# 3.net
KiCad netlist of a schematic drawn in Altium Designer
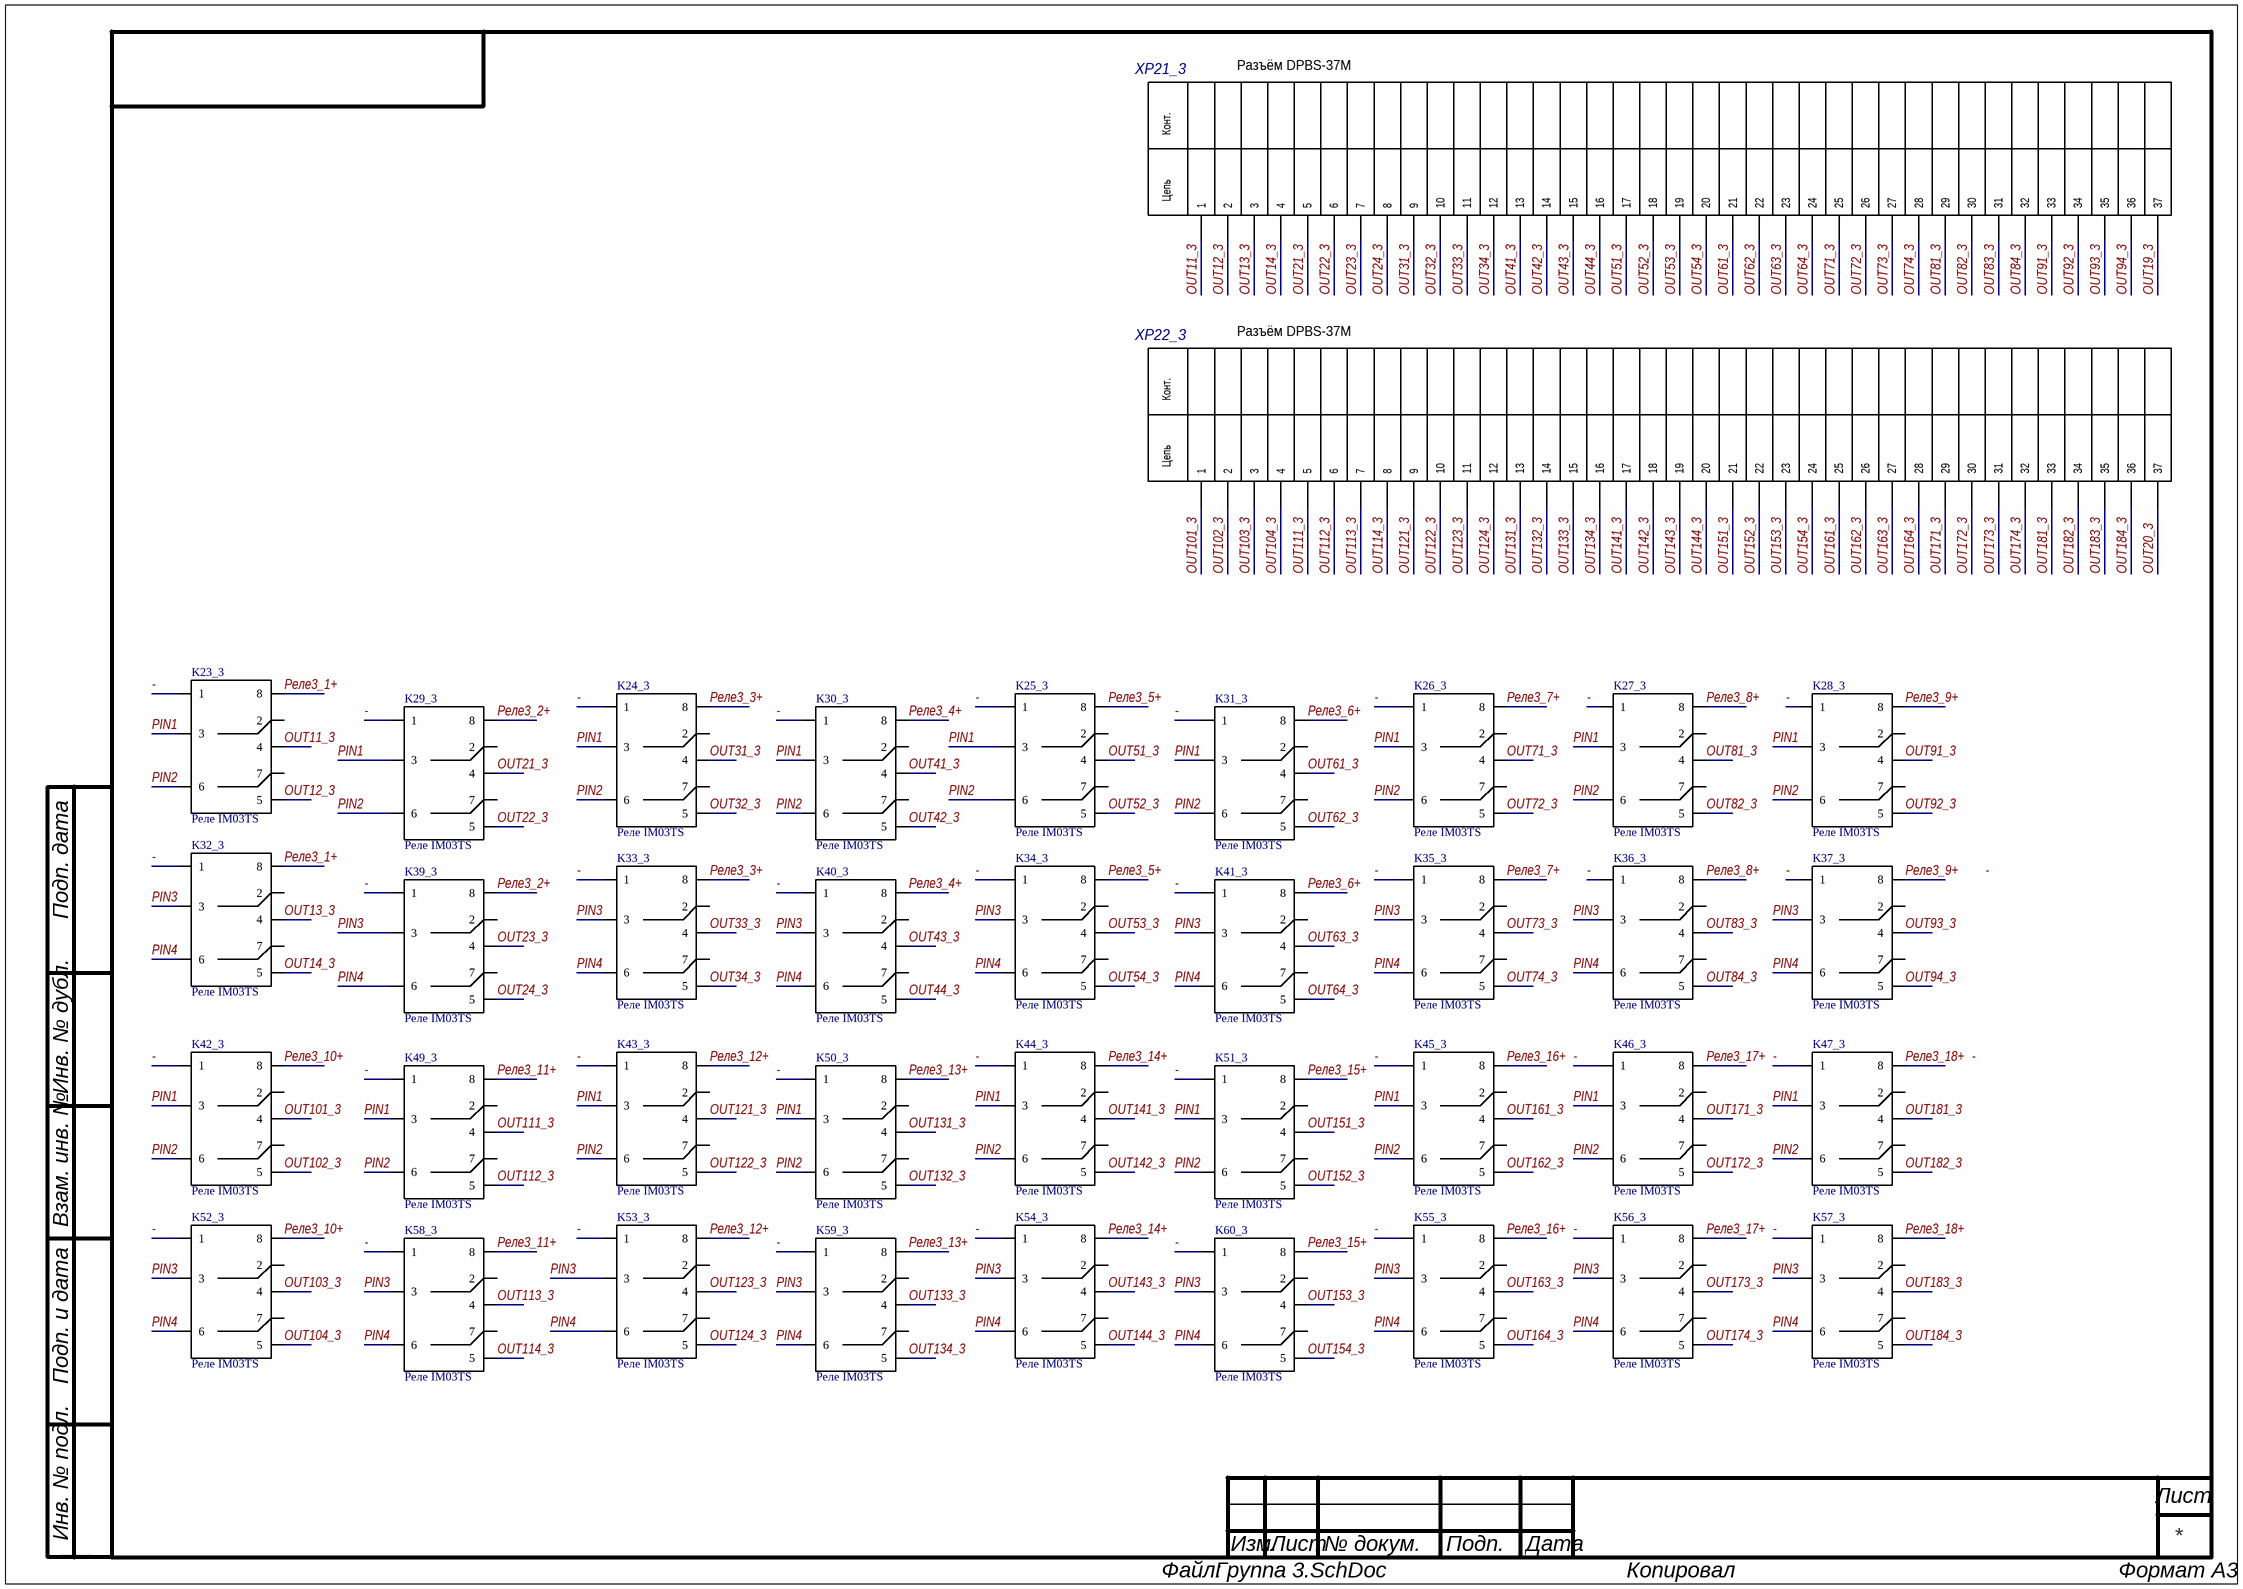
[diagram p0: Группа 3.SchDoc]

(export (version "E")
  (design (tool "Eeschema 10.0.6"))
  (components
    (comp (ref "K23_3")
      (value "Реле IM03TS")
      (footprint "IM03TS")
      (description "Реле")
      (libsource (lib "MainLibrary") (part "IM03TS"))
    )
    (comp (ref "K24_3")
      (value "Реле IM03TS")
      (footprint "IM03TS")
      (description "Реле")
      (libsource (lib "MainLibrary") (part "IM03TS"))
    )
    (comp (ref "K25_3")
      (value "Реле IM03TS")
      (footprint "IM03TS")
      (description "Реле")
      (libsource (lib "MainLibrary") (part "IM03TS"))
    )
    (comp (ref "K26_3")
      (value "Реле IM03TS")
      (footprint "IM03TS")
      (description "Реле")
      (libsource (lib "MainLibrary") (part "IM03TS"))
    )
    (comp (ref "K27_3")
      (value "Реле IM03TS")
      (footprint "IM03TS")
      (description "Реле")
      (libsource (lib "MainLibrary") (part "IM03TS"))
    )
    (comp (ref "K28_3")
      (value "Реле IM03TS")
      (footprint "IM03TS")
      (description "Реле")
      (libsource (lib "MainLibrary") (part "IM03TS"))
    )
    (comp (ref "K29_3")
      (value "Реле IM03TS")
      (footprint "IM03TS")
      (description "Реле")
      (libsource (lib "MainLibrary") (part "IM03TS"))
    )
    (comp (ref "K30_3")
      (value "Реле IM03TS")
      (footprint "IM03TS")
      (description "Реле")
      (libsource (lib "MainLibrary") (part "IM03TS"))
    )
    (comp (ref "K31_3")
      (value "Реле IM03TS")
      (footprint "IM03TS")
      (description "Реле")
      (libsource (lib "MainLibrary") (part "IM03TS"))
    )
    (comp (ref "K32_3")
      (value "Реле IM03TS")
      (footprint "IM03TS")
      (description "Реле")
      (libsource (lib "MainLibrary") (part "IM03TS"))
    )
    (comp (ref "K33_3")
      (value "Реле IM03TS")
      (footprint "IM03TS")
      (description "Реле")
      (libsource (lib "MainLibrary") (part "IM03TS"))
    )
    (comp (ref "K34_3")
      (value "Реле IM03TS")
      (footprint "IM03TS")
      (description "Реле")
      (libsource (lib "MainLibrary") (part "IM03TS"))
    )
    (comp (ref "K35_3")
      (value "Реле IM03TS")
      (footprint "IM03TS")
      (description "Реле")
      (libsource (lib "MainLibrary") (part "IM03TS"))
    )
    (comp (ref "K36_3")
      (value "Реле IM03TS")
      (footprint "IM03TS")
      (description "Реле")
      (libsource (lib "MainLibrary") (part "IM03TS"))
    )
    (comp (ref "K37_3")
      (value "Реле IM03TS")
      (footprint "IM03TS")
      (description "Реле")
      (libsource (lib "MainLibrary") (part "IM03TS"))
    )
    (comp (ref "K39_3")
      (value "Реле IM03TS")
      (footprint "IM03TS")
      (description "Реле")
      (libsource (lib "MainLibrary") (part "IM03TS"))
    )
    (comp (ref "K40_3")
      (value "Реле IM03TS")
      (footprint "IM03TS")
      (description "Реле")
      (libsource (lib "MainLibrary") (part "IM03TS"))
    )
    (comp (ref "K41_3")
      (value "Реле IM03TS")
      (footprint "IM03TS")
      (description "Реле")
      (libsource (lib "MainLibrary") (part "IM03TS"))
    )
    (comp (ref "K42_3")
      (value "Реле IM03TS")
      (footprint "IM03TS")
      (description "Реле")
      (libsource (lib "MainLibrary") (part "IM03TS"))
    )
    (comp (ref "K43_3")
      (value "Реле IM03TS")
      (footprint "IM03TS")
      (description "Реле")
      (libsource (lib "MainLibrary") (part "IM03TS"))
    )
    (comp (ref "K44_3")
      (value "Реле IM03TS")
      (footprint "IM03TS")
      (description "Реле")
      (libsource (lib "MainLibrary") (part "IM03TS"))
    )
    (comp (ref "K45_3")
      (value "Реле IM03TS")
      (footprint "IM03TS")
      (description "Реле")
      (libsource (lib "MainLibrary") (part "IM03TS"))
    )
    (comp (ref "K46_3")
      (value "Реле IM03TS")
      (footprint "IM03TS")
      (description "Реле")
      (libsource (lib "MainLibrary") (part "IM03TS"))
    )
    (comp (ref "K47_3")
      (value "Реле IM03TS")
      (footprint "IM03TS")
      (description "Реле")
      (libsource (lib "MainLibrary") (part "IM03TS"))
    )
    (comp (ref "K49_3")
      (value "Реле IM03TS")
      (footprint "IM03TS")
      (description "Реле")
      (libsource (lib "MainLibrary") (part "IM03TS"))
    )
    (comp (ref "K50_3")
      (value "Реле IM03TS")
      (footprint "IM03TS")
      (description "Реле")
      (libsource (lib "MainLibrary") (part "IM03TS"))
    )
    (comp (ref "K51_3")
      (value "Реле IM03TS")
      (footprint "IM03TS")
      (description "Реле")
      (libsource (lib "MainLibrary") (part "IM03TS"))
    )
    (comp (ref "K52_3")
      (value "Реле IM03TS")
      (footprint "IM03TS")
      (description "Реле")
      (libsource (lib "MainLibrary") (part "IM03TS"))
    )
    (comp (ref "K53_3")
      (value "Реле IM03TS")
      (footprint "IM03TS")
      (description "Реле")
      (libsource (lib "MainLibrary") (part "IM03TS"))
    )
    (comp (ref "K54_3")
      (value "Реле IM03TS")
      (footprint "IM03TS")
      (description "Реле")
      (libsource (lib "MainLibrary") (part "IM03TS"))
    )
    (comp (ref "K55_3")
      (value "Реле IM03TS")
      (footprint "IM03TS")
      (description "Реле")
      (libsource (lib "MainLibrary") (part "IM03TS"))
    )
    (comp (ref "K56_3")
      (value "Реле IM03TS")
      (footprint "IM03TS")
      (description "Реле")
      (libsource (lib "MainLibrary") (part "IM03TS"))
    )
    (comp (ref "K57_3")
      (value "Реле IM03TS")
      (footprint "IM03TS")
      (description "Реле")
      (libsource (lib "MainLibrary") (part "IM03TS"))
    )
    (comp (ref "K58_3")
      (value "Реле IM03TS")
      (footprint "IM03TS")
      (description "Реле")
      (libsource (lib "MainLibrary") (part "IM03TS"))
    )
    (comp (ref "K59_3")
      (value "Реле IM03TS")
      (footprint "IM03TS")
      (description "Реле")
      (libsource (lib "MainLibrary") (part "IM03TS"))
    )
    (comp (ref "K60_3")
      (value "Реле IM03TS")
      (footprint "IM03TS")
      (description "Реле")
      (libsource (lib "MainLibrary") (part "IM03TS"))
    )
    (comp (ref "XP21_3")
      (value "Разъём DPBS-37M")
      (footprint "DPBS-37M")
      (libsource (lib "MainLibrary") (part "DPBS-37M"))
    )
    (comp (ref "XP22_3")
      (value "Разъём DPBS-37M")
      (footprint "DPBS-37M")
      (libsource (lib "MainLibrary") (part "DPBS-37M"))
    )
  )
  (nets
    (net (code "1") (name "/-") (class "Default")
      (node (ref "K23_3") (pin "1") (pinfunction "1_1") (pintype "passive"))
      (node (ref "K24_3") (pin "1") (pinfunction "1_1") (pintype "passive"))
      (node (ref "K25_3") (pin "1") (pinfunction "1_1") (pintype "passive"))
      (node (ref "K26_3") (pin "1") (pinfunction "1_1") (pintype "passive"))
      (node (ref "K27_3") (pin "1") (pinfunction "1_1") (pintype "passive"))
      (node (ref "K28_3") (pin "1") (pinfunction "1_1") (pintype "passive"))
      (node (ref "K29_3") (pin "1") (pinfunction "1_1") (pintype "passive"))
      (node (ref "K30_3") (pin "1") (pinfunction "1_1") (pintype "passive"))
      (node (ref "K31_3") (pin "1") (pinfunction "1_1") (pintype "passive"))
      (node (ref "K32_3") (pin "1") (pinfunction "1_1") (pintype "passive"))
      (node (ref "K33_3") (pin "1") (pinfunction "1_1") (pintype "passive"))
      (node (ref "K34_3") (pin "1") (pinfunction "1_1") (pintype "passive"))
      (node (ref "K35_3") (pin "1") (pinfunction "1_1") (pintype "passive"))
      (node (ref "K36_3") (pin "1") (pinfunction "1_1") (pintype "passive"))
      (node (ref "K37_3") (pin "1") (pinfunction "1_1") (pintype "passive"))
      (node (ref "K39_3") (pin "1") (pinfunction "1_1") (pintype "passive"))
      (node (ref "K40_3") (pin "1") (pinfunction "1_1") (pintype "passive"))
      (node (ref "K41_3") (pin "1") (pinfunction "1_1") (pintype "passive"))
      (node (ref "K42_3") (pin "1") (pinfunction "1_1") (pintype "passive"))
      (node (ref "K43_3") (pin "1") (pinfunction "1_1") (pintype "passive"))
      (node (ref "K44_3") (pin "1") (pinfunction "1_1") (pintype "passive"))
      (node (ref "K45_3") (pin "1") (pinfunction "1_1") (pintype "passive"))
      (node (ref "K46_3") (pin "1") (pinfunction "1_1") (pintype "passive"))
      (node (ref "K47_3") (pin "1") (pinfunction "1_1") (pintype "passive"))
      (node (ref "K49_3") (pin "1") (pinfunction "1_1") (pintype "passive"))
      (node (ref "K50_3") (pin "1") (pinfunction "1_1") (pintype "passive"))
      (node (ref "K51_3") (pin "1") (pinfunction "1_1") (pintype "passive"))
      (node (ref "K52_3") (pin "1") (pinfunction "1_1") (pintype "passive"))
      (node (ref "K53_3") (pin "1") (pinfunction "1_1") (pintype "passive"))
      (node (ref "K54_3") (pin "1") (pinfunction "1_1") (pintype "passive"))
      (node (ref "K55_3") (pin "1") (pinfunction "1_1") (pintype "passive"))
      (node (ref "K56_3") (pin "1") (pinfunction "1_1") (pintype "passive"))
      (node (ref "K57_3") (pin "1") (pinfunction "1_1") (pintype "passive"))
      (node (ref "K58_3") (pin "1") (pinfunction "1_1") (pintype "passive"))
      (node (ref "K59_3") (pin "1") (pinfunction "1_1") (pintype "passive"))
      (node (ref "K60_3") (pin "1") (pinfunction "1_1") (pintype "passive"))
    )
    (net (code "2") (name "/OUT11_3") (class "Default")
      (node (ref "K23_3") (pin "4") (pinfunction "4_4") (pintype "passive"))
      (node (ref "XP21_3") (pin "1") (pinfunction "1_1") (pintype "passive"))
    )
    (net (code "3") (name "/OUT12_3") (class "Default")
      (node (ref "K23_3") (pin "5") (pinfunction "5_5") (pintype "passive"))
      (node (ref "XP21_3") (pin "2") (pinfunction "2_2") (pintype "passive"))
    )
    (net (code "4") (name "/OUT13_3") (class "Default")
      (node (ref "K32_3") (pin "4") (pinfunction "4_4") (pintype "passive"))
      (node (ref "XP21_3") (pin "3") (pinfunction "3_3") (pintype "passive"))
    )
    (net (code "5") (name "/OUT14_3") (class "Default")
      (node (ref "K32_3") (pin "5") (pinfunction "5_5") (pintype "passive"))
      (node (ref "XP21_3") (pin "4") (pinfunction "4_4") (pintype "passive"))
    )
    (net (code "6") (name "/OUT19_3") (class "Default")
      (node (ref "XP21_3") (pin "37") (pinfunction "37_37") (pintype "passive"))
    )
    (net (code "7") (name "/OUT20_3") (class "Default")
      (node (ref "XP22_3") (pin "37") (pinfunction "37_37") (pintype "passive"))
    )
    (net (code "8") (name "/OUT21_3") (class "Default")
      (node (ref "K29_3") (pin "4") (pinfunction "4_4") (pintype "passive"))
      (node (ref "XP21_3") (pin "5") (pinfunction "5_5") (pintype "passive"))
    )
    (net (code "9") (name "/OUT22_3") (class "Default")
      (node (ref "K29_3") (pin "5") (pinfunction "5_5") (pintype "passive"))
      (node (ref "XP21_3") (pin "6") (pinfunction "6_6") (pintype "passive"))
    )
    (net (code "10") (name "/OUT23_3") (class "Default")
      (node (ref "K39_3") (pin "4") (pinfunction "4_4") (pintype "passive"))
      (node (ref "XP21_3") (pin "7") (pinfunction "7_7") (pintype "passive"))
    )
    (net (code "11") (name "/OUT24_3") (class "Default")
      (node (ref "K39_3") (pin "5") (pinfunction "5_5") (pintype "passive"))
      (node (ref "XP21_3") (pin "8") (pinfunction "8_8") (pintype "passive"))
    )
    (net (code "12") (name "/OUT31_3") (class "Default")
      (node (ref "K24_3") (pin "4") (pinfunction "4_4") (pintype "passive"))
      (node (ref "XP21_3") (pin "9") (pinfunction "9_9") (pintype "passive"))
    )
    (net (code "13") (name "/OUT32_3") (class "Default")
      (node (ref "K24_3") (pin "5") (pinfunction "5_5") (pintype "passive"))
      (node (ref "XP21_3") (pin "10") (pinfunction "10_10") (pintype "passive"))
    )
    (net (code "14") (name "/OUT33_3") (class "Default")
      (node (ref "K33_3") (pin "4") (pinfunction "4_4") (pintype "passive"))
      (node (ref "XP21_3") (pin "11") (pinfunction "11_11") (pintype "passive"))
    )
    (net (code "15") (name "/OUT34_3") (class "Default")
      (node (ref "K33_3") (pin "5") (pinfunction "5_5") (pintype "passive"))
      (node (ref "XP21_3") (pin "12") (pinfunction "12_12") (pintype "passive"))
    )
    (net (code "16") (name "/OUT41_3") (class "Default")
      (node (ref "K30_3") (pin "4") (pinfunction "4_4") (pintype "passive"))
      (node (ref "XP21_3") (pin "13") (pinfunction "13_13") (pintype "passive"))
    )
    (net (code "17") (name "/OUT42_3") (class "Default")
      (node (ref "K30_3") (pin "5") (pinfunction "5_5") (pintype "passive"))
      (node (ref "XP21_3") (pin "14") (pinfunction "14_14") (pintype "passive"))
    )
    (net (code "18") (name "/OUT43_3") (class "Default")
      (node (ref "K40_3") (pin "4") (pinfunction "4_4") (pintype "passive"))
      (node (ref "XP21_3") (pin "15") (pinfunction "15_15") (pintype "passive"))
    )
    (net (code "19") (name "/OUT44_3") (class "Default")
      (node (ref "K40_3") (pin "5") (pinfunction "5_5") (pintype "passive"))
      (node (ref "XP21_3") (pin "16") (pinfunction "16_16") (pintype "passive"))
    )
    (net (code "20") (name "/OUT51_3") (class "Default")
      (node (ref "K25_3") (pin "4") (pinfunction "4_4") (pintype "passive"))
      (node (ref "XP21_3") (pin "17") (pinfunction "17_17") (pintype "passive"))
    )
    (net (code "21") (name "/OUT52_3") (class "Default")
      (node (ref "K25_3") (pin "5") (pinfunction "5_5") (pintype "passive"))
      (node (ref "XP21_3") (pin "18") (pinfunction "18_18") (pintype "passive"))
    )
    (net (code "22") (name "/OUT53_3") (class "Default")
      (node (ref "K34_3") (pin "4") (pinfunction "4_4") (pintype "passive"))
      (node (ref "XP21_3") (pin "19") (pinfunction "19_19") (pintype "passive"))
    )
    (net (code "23") (name "/OUT54_3") (class "Default")
      (node (ref "K34_3") (pin "5") (pinfunction "5_5") (pintype "passive"))
      (node (ref "XP21_3") (pin "20") (pinfunction "20_20") (pintype "passive"))
    )
    (net (code "24") (name "/OUT61_3") (class "Default")
      (node (ref "K31_3") (pin "4") (pinfunction "4_4") (pintype "passive"))
      (node (ref "XP21_3") (pin "21") (pinfunction "21_21") (pintype "passive"))
    )
    (net (code "25") (name "/OUT62_3") (class "Default")
      (node (ref "K31_3") (pin "5") (pinfunction "5_5") (pintype "passive"))
      (node (ref "XP21_3") (pin "22") (pinfunction "22_22") (pintype "passive"))
    )
    (net (code "26") (name "/OUT63_3") (class "Default")
      (node (ref "K41_3") (pin "4") (pinfunction "4_4") (pintype "passive"))
      (node (ref "XP21_3") (pin "23") (pinfunction "23_23") (pintype "passive"))
    )
    (net (code "27") (name "/OUT64_3") (class "Default")
      (node (ref "K41_3") (pin "5") (pinfunction "5_5") (pintype "passive"))
      (node (ref "XP21_3") (pin "24") (pinfunction "24_24") (pintype "passive"))
    )
    (net (code "28") (name "/OUT71_3") (class "Default")
      (node (ref "K26_3") (pin "4") (pinfunction "4_4") (pintype "passive"))
      (node (ref "XP21_3") (pin "25") (pinfunction "25_25") (pintype "passive"))
    )
    (net (code "29") (name "/OUT72_3") (class "Default")
      (node (ref "K26_3") (pin "5") (pinfunction "5_5") (pintype "passive"))
      (node (ref "XP21_3") (pin "26") (pinfunction "26_26") (pintype "passive"))
    )
    (net (code "30") (name "/OUT73_3") (class "Default")
      (node (ref "K35_3") (pin "4") (pinfunction "4_4") (pintype "passive"))
      (node (ref "XP21_3") (pin "27") (pinfunction "27_27") (pintype "passive"))
    )
    (net (code "31") (name "/OUT74_3") (class "Default")
      (node (ref "K35_3") (pin "5") (pinfunction "5_5") (pintype "passive"))
      (node (ref "XP21_3") (pin "28") (pinfunction "28_28") (pintype "passive"))
    )
    (net (code "32") (name "/OUT81_3") (class "Default")
      (node (ref "K27_3") (pin "4") (pinfunction "4_4") (pintype "passive"))
      (node (ref "XP21_3") (pin "29") (pinfunction "29_29") (pintype "passive"))
    )
    (net (code "33") (name "/OUT82_3") (class "Default")
      (node (ref "K27_3") (pin "5") (pinfunction "5_5") (pintype "passive"))
      (node (ref "XP21_3") (pin "30") (pinfunction "30_30") (pintype "passive"))
    )
    (net (code "34") (name "/OUT83_3") (class "Default")
      (node (ref "K36_3") (pin "4") (pinfunction "4_4") (pintype "passive"))
      (node (ref "XP21_3") (pin "31") (pinfunction "31_31") (pintype "passive"))
    )
    (net (code "35") (name "/OUT84_3") (class "Default")
      (node (ref "K36_3") (pin "5") (pinfunction "5_5") (pintype "passive"))
      (node (ref "XP21_3") (pin "32") (pinfunction "32_32") (pintype "passive"))
    )
    (net (code "36") (name "/OUT91_3") (class "Default")
      (node (ref "K28_3") (pin "4") (pinfunction "4_4") (pintype "passive"))
      (node (ref "XP21_3") (pin "33") (pinfunction "33_33") (pintype "passive"))
    )
    (net (code "37") (name "/OUT92_3") (class "Default")
      (node (ref "K28_3") (pin "5") (pinfunction "5_5") (pintype "passive"))
      (node (ref "XP21_3") (pin "34") (pinfunction "34_34") (pintype "passive"))
    )
    (net (code "38") (name "/OUT93_3") (class "Default")
      (node (ref "K37_3") (pin "4") (pinfunction "4_4") (pintype "passive"))
      (node (ref "XP21_3") (pin "35") (pinfunction "35_35") (pintype "passive"))
    )
    (net (code "39") (name "/OUT94_3") (class "Default")
      (node (ref "K37_3") (pin "5") (pinfunction "5_5") (pintype "passive"))
      (node (ref "XP21_3") (pin "36") (pinfunction "36_36") (pintype "passive"))
    )
    (net (code "40") (name "/OUT101_3") (class "Default")
      (node (ref "K42_3") (pin "4") (pinfunction "4_4") (pintype "passive"))
      (node (ref "XP22_3") (pin "1") (pinfunction "1_1") (pintype "passive"))
    )
    (net (code "41") (name "/OUT102_3") (class "Default")
      (node (ref "K42_3") (pin "5") (pinfunction "5_5") (pintype "passive"))
      (node (ref "XP22_3") (pin "2") (pinfunction "2_2") (pintype "passive"))
    )
    (net (code "42") (name "/OUT103_3") (class "Default")
      (node (ref "K52_3") (pin "4") (pinfunction "4_4") (pintype "passive"))
      (node (ref "XP22_3") (pin "3") (pinfunction "3_3") (pintype "passive"))
    )
    (net (code "43") (name "/OUT104_3") (class "Default")
      (node (ref "K52_3") (pin "5") (pinfunction "5_5") (pintype "passive"))
      (node (ref "XP22_3") (pin "4") (pinfunction "4_4") (pintype "passive"))
    )
    (net (code "44") (name "/OUT111_3") (class "Default")
      (node (ref "K49_3") (pin "4") (pinfunction "4_4") (pintype "passive"))
      (node (ref "XP22_3") (pin "5") (pinfunction "5_5") (pintype "passive"))
    )
    (net (code "45") (name "/OUT112_3") (class "Default")
      (node (ref "K49_3") (pin "5") (pinfunction "5_5") (pintype "passive"))
      (node (ref "XP22_3") (pin "6") (pinfunction "6_6") (pintype "passive"))
    )
    (net (code "46") (name "/OUT113_3") (class "Default")
      (node (ref "K58_3") (pin "4") (pinfunction "4_4") (pintype "passive"))
      (node (ref "XP22_3") (pin "7") (pinfunction "7_7") (pintype "passive"))
    )
    (net (code "47") (name "/OUT114_3") (class "Default")
      (node (ref "K58_3") (pin "5") (pinfunction "5_5") (pintype "passive"))
      (node (ref "XP22_3") (pin "8") (pinfunction "8_8") (pintype "passive"))
    )
    (net (code "48") (name "/OUT121_3") (class "Default")
      (node (ref "K43_3") (pin "4") (pinfunction "4_4") (pintype "passive"))
      (node (ref "XP22_3") (pin "9") (pinfunction "9_9") (pintype "passive"))
    )
    (net (code "49") (name "/OUT122_3") (class "Default")
      (node (ref "K43_3") (pin "5") (pinfunction "5_5") (pintype "passive"))
      (node (ref "XP22_3") (pin "10") (pinfunction "10_10") (pintype "passive"))
    )
    (net (code "50") (name "/OUT123_3") (class "Default")
      (node (ref "K53_3") (pin "4") (pinfunction "4_4") (pintype "passive"))
      (node (ref "XP22_3") (pin "11") (pinfunction "11_11") (pintype "passive"))
    )
    (net (code "51") (name "/OUT124_3") (class "Default")
      (node (ref "K53_3") (pin "5") (pinfunction "5_5") (pintype "passive"))
      (node (ref "XP22_3") (pin "12") (pinfunction "12_12") (pintype "passive"))
    )
    (net (code "52") (name "/OUT131_3") (class "Default")
      (node (ref "K50_3") (pin "4") (pinfunction "4_4") (pintype "passive"))
      (node (ref "XP22_3") (pin "13") (pinfunction "13_13") (pintype "passive"))
    )
    (net (code "53") (name "/OUT132_3") (class "Default")
      (node (ref "K50_3") (pin "5") (pinfunction "5_5") (pintype "passive"))
      (node (ref "XP22_3") (pin "14") (pinfunction "14_14") (pintype "passive"))
    )
    (net (code "54") (name "/OUT133_3") (class "Default")
      (node (ref "K59_3") (pin "4") (pinfunction "4_4") (pintype "passive"))
      (node (ref "XP22_3") (pin "15") (pinfunction "15_15") (pintype "passive"))
    )
    (net (code "55") (name "/OUT134_3") (class "Default")
      (node (ref "K59_3") (pin "5") (pinfunction "5_5") (pintype "passive"))
      (node (ref "XP22_3") (pin "16") (pinfunction "16_16") (pintype "passive"))
    )
    (net (code "56") (name "/OUT141_3") (class "Default")
      (node (ref "K44_3") (pin "4") (pinfunction "4_4") (pintype "passive"))
      (node (ref "XP22_3") (pin "17") (pinfunction "17_17") (pintype "passive"))
    )
    (net (code "57") (name "/OUT142_3") (class "Default")
      (node (ref "K44_3") (pin "5") (pinfunction "5_5") (pintype "passive"))
      (node (ref "XP22_3") (pin "18") (pinfunction "18_18") (pintype "passive"))
    )
    (net (code "58") (name "/OUT143_3") (class "Default")
      (node (ref "K54_3") (pin "4") (pinfunction "4_4") (pintype "passive"))
      (node (ref "XP22_3") (pin "19") (pinfunction "19_19") (pintype "passive"))
    )
    (net (code "59") (name "/OUT144_3") (class "Default")
      (node (ref "K54_3") (pin "5") (pinfunction "5_5") (pintype "passive"))
      (node (ref "XP22_3") (pin "20") (pinfunction "20_20") (pintype "passive"))
    )
    (net (code "60") (name "/OUT151_3") (class "Default")
      (node (ref "K51_3") (pin "4") (pinfunction "4_4") (pintype "passive"))
      (node (ref "XP22_3") (pin "21") (pinfunction "21_21") (pintype "passive"))
    )
    (net (code "61") (name "/OUT152_3") (class "Default")
      (node (ref "K51_3") (pin "5") (pinfunction "5_5") (pintype "passive"))
      (node (ref "XP22_3") (pin "22") (pinfunction "22_22") (pintype "passive"))
    )
    (net (code "62") (name "/OUT153_3") (class "Default")
      (node (ref "K60_3") (pin "4") (pinfunction "4_4") (pintype "passive"))
      (node (ref "XP22_3") (pin "23") (pinfunction "23_23") (pintype "passive"))
    )
    (net (code "63") (name "/OUT154_3") (class "Default")
      (node (ref "K60_3") (pin "5") (pinfunction "5_5") (pintype "passive"))
      (node (ref "XP22_3") (pin "24") (pinfunction "24_24") (pintype "passive"))
    )
    (net (code "64") (name "/OUT161_3") (class "Default")
      (node (ref "K45_3") (pin "4") (pinfunction "4_4") (pintype "passive"))
      (node (ref "XP22_3") (pin "25") (pinfunction "25_25") (pintype "passive"))
    )
    (net (code "65") (name "/OUT162_3") (class "Default")
      (node (ref "K45_3") (pin "5") (pinfunction "5_5") (pintype "passive"))
      (node (ref "XP22_3") (pin "26") (pinfunction "26_26") (pintype "passive"))
    )
    (net (code "66") (name "/OUT163_3") (class "Default")
      (node (ref "K55_3") (pin "4") (pinfunction "4_4") (pintype "passive"))
      (node (ref "XP22_3") (pin "27") (pinfunction "27_27") (pintype "passive"))
    )
    (net (code "67") (name "/OUT164_3") (class "Default")
      (node (ref "K55_3") (pin "5") (pinfunction "5_5") (pintype "passive"))
      (node (ref "XP22_3") (pin "28") (pinfunction "28_28") (pintype "passive"))
    )
    (net (code "68") (name "/OUT171_3") (class "Default")
      (node (ref "K46_3") (pin "4") (pinfunction "4_4") (pintype "passive"))
      (node (ref "XP22_3") (pin "29") (pinfunction "29_29") (pintype "passive"))
    )
    (net (code "69") (name "/OUT172_3") (class "Default")
      (node (ref "K46_3") (pin "5") (pinfunction "5_5") (pintype "passive"))
      (node (ref "XP22_3") (pin "30") (pinfunction "30_30") (pintype "passive"))
    )
    (net (code "70") (name "/OUT173_3") (class "Default")
      (node (ref "K56_3") (pin "4") (pinfunction "4_4") (pintype "passive"))
      (node (ref "XP22_3") (pin "31") (pinfunction "31_31") (pintype "passive"))
    )
    (net (code "71") (name "/OUT174_3") (class "Default")
      (node (ref "K56_3") (pin "5") (pinfunction "5_5") (pintype "passive"))
      (node (ref "XP22_3") (pin "32") (pinfunction "32_32") (pintype "passive"))
    )
    (net (code "72") (name "/OUT181_3") (class "Default")
      (node (ref "K47_3") (pin "4") (pinfunction "4_4") (pintype "passive"))
      (node (ref "XP22_3") (pin "33") (pinfunction "33_33") (pintype "passive"))
    )
    (net (code "73") (name "/OUT182_3") (class "Default")
      (node (ref "K47_3") (pin "5") (pinfunction "5_5") (pintype "passive"))
      (node (ref "XP22_3") (pin "34") (pinfunction "34_34") (pintype "passive"))
    )
    (net (code "74") (name "/OUT183_3") (class "Default")
      (node (ref "K57_3") (pin "4") (pinfunction "4_4") (pintype "passive"))
      (node (ref "XP22_3") (pin "35") (pinfunction "35_35") (pintype "passive"))
    )
    (net (code "75") (name "/OUT184_3") (class "Default")
      (node (ref "K57_3") (pin "5") (pinfunction "5_5") (pintype "passive"))
      (node (ref "XP22_3") (pin "36") (pinfunction "36_36") (pintype "passive"))
    )
    (net (code "76") (name "/PIN1") (class "Default")
      (node (ref "K23_3") (pin "3") (pinfunction "3_3") (pintype "passive"))
      (node (ref "K24_3") (pin "3") (pinfunction "3_3") (pintype "passive"))
      (node (ref "K25_3") (pin "3") (pinfunction "3_3") (pintype "passive"))
      (node (ref "K26_3") (pin "3") (pinfunction "3_3") (pintype "passive"))
      (node (ref "K27_3") (pin "3") (pinfunction "3_3") (pintype "passive"))
      (node (ref "K28_3") (pin "3") (pinfunction "3_3") (pintype "passive"))
      (node (ref "K29_3") (pin "3") (pinfunction "3_3") (pintype "passive"))
      (node (ref "K30_3") (pin "3") (pinfunction "3_3") (pintype "passive"))
      (node (ref "K31_3") (pin "3") (pinfunction "3_3") (pintype "passive"))
      (node (ref "K42_3") (pin "3") (pinfunction "3_3") (pintype "passive"))
      (node (ref "K43_3") (pin "3") (pinfunction "3_3") (pintype "passive"))
      (node (ref "K44_3") (pin "3") (pinfunction "3_3") (pintype "passive"))
      (node (ref "K45_3") (pin "3") (pinfunction "3_3") (pintype "passive"))
      (node (ref "K46_3") (pin "3") (pinfunction "3_3") (pintype "passive"))
      (node (ref "K47_3") (pin "3") (pinfunction "3_3") (pintype "passive"))
      (node (ref "K49_3") (pin "3") (pinfunction "3_3") (pintype "passive"))
      (node (ref "K50_3") (pin "3") (pinfunction "3_3") (pintype "passive"))
      (node (ref "K51_3") (pin "3") (pinfunction "3_3") (pintype "passive"))
    )
    (net (code "77") (name "/PIN2") (class "Default")
      (node (ref "K23_3") (pin "6") (pinfunction "6_6") (pintype "passive"))
      (node (ref "K24_3") (pin "6") (pinfunction "6_6") (pintype "passive"))
      (node (ref "K25_3") (pin "6") (pinfunction "6_6") (pintype "passive"))
      (node (ref "K26_3") (pin "6") (pinfunction "6_6") (pintype "passive"))
      (node (ref "K27_3") (pin "6") (pinfunction "6_6") (pintype "passive"))
      (node (ref "K28_3") (pin "6") (pinfunction "6_6") (pintype "passive"))
      (node (ref "K29_3") (pin "6") (pinfunction "6_6") (pintype "passive"))
      (node (ref "K30_3") (pin "6") (pinfunction "6_6") (pintype "passive"))
      (node (ref "K31_3") (pin "6") (pinfunction "6_6") (pintype "passive"))
      (node (ref "K42_3") (pin "6") (pinfunction "6_6") (pintype "passive"))
      (node (ref "K43_3") (pin "6") (pinfunction "6_6") (pintype "passive"))
      (node (ref "K44_3") (pin "6") (pinfunction "6_6") (pintype "passive"))
      (node (ref "K45_3") (pin "6") (pinfunction "6_6") (pintype "passive"))
      (node (ref "K46_3") (pin "6") (pinfunction "6_6") (pintype "passive"))
      (node (ref "K47_3") (pin "6") (pinfunction "6_6") (pintype "passive"))
      (node (ref "K49_3") (pin "6") (pinfunction "6_6") (pintype "passive"))
      (node (ref "K50_3") (pin "6") (pinfunction "6_6") (pintype "passive"))
      (node (ref "K51_3") (pin "6") (pinfunction "6_6") (pintype "passive"))
    )
    (net (code "78") (name "/PIN3") (class "Default")
      (node (ref "K32_3") (pin "3") (pinfunction "3_3") (pintype "passive"))
      (node (ref "K33_3") (pin "3") (pinfunction "3_3") (pintype "passive"))
      (node (ref "K34_3") (pin "3") (pinfunction "3_3") (pintype "passive"))
      (node (ref "K35_3") (pin "3") (pinfunction "3_3") (pintype "passive"))
      (node (ref "K36_3") (pin "3") (pinfunction "3_3") (pintype "passive"))
      (node (ref "K37_3") (pin "3") (pinfunction "3_3") (pintype "passive"))
      (node (ref "K39_3") (pin "3") (pinfunction "3_3") (pintype "passive"))
      (node (ref "K40_3") (pin "3") (pinfunction "3_3") (pintype "passive"))
      (node (ref "K41_3") (pin "3") (pinfunction "3_3") (pintype "passive"))
      (node (ref "K52_3") (pin "3") (pinfunction "3_3") (pintype "passive"))
      (node (ref "K53_3") (pin "3") (pinfunction "3_3") (pintype "passive"))
      (node (ref "K54_3") (pin "3") (pinfunction "3_3") (pintype "passive"))
      (node (ref "K55_3") (pin "3") (pinfunction "3_3") (pintype "passive"))
      (node (ref "K56_3") (pin "3") (pinfunction "3_3") (pintype "passive"))
      (node (ref "K57_3") (pin "3") (pinfunction "3_3") (pintype "passive"))
      (node (ref "K58_3") (pin "3") (pinfunction "3_3") (pintype "passive"))
      (node (ref "K59_3") (pin "3") (pinfunction "3_3") (pintype "passive"))
      (node (ref "K60_3") (pin "3") (pinfunction "3_3") (pintype "passive"))
    )
    (net (code "79") (name "/PIN4") (class "Default")
      (node (ref "K32_3") (pin "6") (pinfunction "6_6") (pintype "passive"))
      (node (ref "K33_3") (pin "6") (pinfunction "6_6") (pintype "passive"))
      (node (ref "K34_3") (pin "6") (pinfunction "6_6") (pintype "passive"))
      (node (ref "K35_3") (pin "6") (pinfunction "6_6") (pintype "passive"))
      (node (ref "K36_3") (pin "6") (pinfunction "6_6") (pintype "passive"))
      (node (ref "K37_3") (pin "6") (pinfunction "6_6") (pintype "passive"))
      (node (ref "K39_3") (pin "6") (pinfunction "6_6") (pintype "passive"))
      (node (ref "K40_3") (pin "6") (pinfunction "6_6") (pintype "passive"))
      (node (ref "K41_3") (pin "6") (pinfunction "6_6") (pintype "passive"))
      (node (ref "K52_3") (pin "6") (pinfunction "6_6") (pintype "passive"))
      (node (ref "K53_3") (pin "6") (pinfunction "6_6") (pintype "passive"))
      (node (ref "K54_3") (pin "6") (pinfunction "6_6") (pintype "passive"))
      (node (ref "K55_3") (pin "6") (pinfunction "6_6") (pintype "passive"))
      (node (ref "K56_3") (pin "6") (pinfunction "6_6") (pintype "passive"))
      (node (ref "K57_3") (pin "6") (pinfunction "6_6") (pintype "passive"))
      (node (ref "K58_3") (pin "6") (pinfunction "6_6") (pintype "passive"))
      (node (ref "K59_3") (pin "6") (pinfunction "6_6") (pintype "passive"))
      (node (ref "K60_3") (pin "6") (pinfunction "6_6") (pintype "passive"))
    )
    (net (code "80") (name "/Реле3_1+") (class "Default")
      (node (ref "K23_3") (pin "8") (pinfunction "8_8") (pintype "passive"))
      (node (ref "K32_3") (pin "8") (pinfunction "8_8") (pintype "passive"))
    )
    (net (code "81") (name "/Реле3_2+") (class "Default")
      (node (ref "K29_3") (pin "8") (pinfunction "8_8") (pintype "passive"))
      (node (ref "K39_3") (pin "8") (pinfunction "8_8") (pintype "passive"))
    )
    (net (code "82") (name "/Реле3_3+") (class "Default")
      (node (ref "K24_3") (pin "8") (pinfunction "8_8") (pintype "passive"))
      (node (ref "K33_3") (pin "8") (pinfunction "8_8") (pintype "passive"))
    )
    (net (code "83") (name "/Реле3_4+") (class "Default")
      (node (ref "K30_3") (pin "8") (pinfunction "8_8") (pintype "passive"))
      (node (ref "K40_3") (pin "8") (pinfunction "8_8") (pintype "passive"))
    )
    (net (code "84") (name "/Реле3_5+") (class "Default")
      (node (ref "K25_3") (pin "8") (pinfunction "8_8") (pintype "passive"))
      (node (ref "K34_3") (pin "8") (pinfunction "8_8") (pintype "passive"))
    )
    (net (code "85") (name "/Реле3_6+") (class "Default")
      (node (ref "K31_3") (pin "8") (pinfunction "8_8") (pintype "passive"))
      (node (ref "K41_3") (pin "8") (pinfunction "8_8") (pintype "passive"))
    )
    (net (code "86") (name "/Реле3_7+") (class "Default")
      (node (ref "K26_3") (pin "8") (pinfunction "8_8") (pintype "passive"))
      (node (ref "K35_3") (pin "8") (pinfunction "8_8") (pintype "passive"))
    )
    (net (code "87") (name "/Реле3_8+") (class "Default")
      (node (ref "K27_3") (pin "8") (pinfunction "8_8") (pintype "passive"))
      (node (ref "K36_3") (pin "8") (pinfunction "8_8") (pintype "passive"))
    )
    (net (code "88") (name "/Реле3_9+") (class "Default")
      (node (ref "K28_3") (pin "8") (pinfunction "8_8") (pintype "passive"))
      (node (ref "K37_3") (pin "8") (pinfunction "8_8") (pintype "passive"))
    )
    (net (code "89") (name "/Реле3_10+") (class "Default")
      (node (ref "K42_3") (pin "8") (pinfunction "8_8") (pintype "passive"))
      (node (ref "K52_3") (pin "8") (pinfunction "8_8") (pintype "passive"))
    )
    (net (code "90") (name "/Реле3_11+") (class "Default")
      (node (ref "K49_3") (pin "8") (pinfunction "8_8") (pintype "passive"))
      (node (ref "K58_3") (pin "8") (pinfunction "8_8") (pintype "passive"))
    )
    (net (code "91") (name "/Реле3_12+") (class "Default")
      (node (ref "K43_3") (pin "8") (pinfunction "8_8") (pintype "passive"))
      (node (ref "K53_3") (pin "8") (pinfunction "8_8") (pintype "passive"))
    )
    (net (code "92") (name "/Реле3_13+") (class "Default")
      (node (ref "K50_3") (pin "8") (pinfunction "8_8") (pintype "passive"))
      (node (ref "K59_3") (pin "8") (pinfunction "8_8") (pintype "passive"))
    )
    (net (code "93") (name "/Реле3_14+") (class "Default")
      (node (ref "K44_3") (pin "8") (pinfunction "8_8") (pintype "passive"))
      (node (ref "K54_3") (pin "8") (pinfunction "8_8") (pintype "passive"))
    )
    (net (code "94") (name "/Реле3_15+") (class "Default")
      (node (ref "K51_3") (pin "8") (pinfunction "8_8") (pintype "passive"))
      (node (ref "K60_3") (pin "8") (pinfunction "8_8") (pintype "passive"))
    )
    (net (code "95") (name "/Реле3_16+") (class "Default")
      (node (ref "K45_3") (pin "8") (pinfunction "8_8") (pintype "passive"))
      (node (ref "K55_3") (pin "8") (pinfunction "8_8") (pintype "passive"))
    )
    (net (code "96") (name "/Реле3_17+") (class "Default")
      (node (ref "K46_3") (pin "8") (pinfunction "8_8") (pintype "passive"))
      (node (ref "K56_3") (pin "8") (pinfunction "8_8") (pintype "passive"))
    )
    (net (code "97") (name "/Реле3_18+") (class "Default")
      (node (ref "K47_3") (pin "8") (pinfunction "8_8") (pintype "passive"))
      (node (ref "K57_3") (pin "8") (pinfunction "8_8") (pintype "passive"))
    )
    (net (code "98") (name "unconnected-(K23_3-Pad2)") (class "Default")
      (node (ref "K23_3") (pin "2") (pinfunction "2_2") (pintype "passive"))
    )
    (net (code "99") (name "unconnected-(K23_3-Pad7)") (class "Default")
      (node (ref "K23_3") (pin "7") (pinfunction "7_7") (pintype "passive"))
    )
    (net (code "100") (name "unconnected-(K24_3-Pad2)") (class "Default")
      (node (ref "K24_3") (pin "2") (pinfunction "2_2") (pintype "passive"))
    )
    (net (code "101") (name "unconnected-(K24_3-Pad7)") (class "Default")
      (node (ref "K24_3") (pin "7") (pinfunction "7_7") (pintype "passive"))
    )
    (net (code "102") (name "unconnected-(K25_3-Pad2)") (class "Default")
      (node (ref "K25_3") (pin "2") (pinfunction "2_2") (pintype "passive"))
    )
    (net (code "103") (name "unconnected-(K25_3-Pad7)") (class "Default")
      (node (ref "K25_3") (pin "7") (pinfunction "7_7") (pintype "passive"))
    )
    (net (code "104") (name "unconnected-(K26_3-Pad2)") (class "Default")
      (node (ref "K26_3") (pin "2") (pinfunction "2_2") (pintype "passive"))
    )
    (net (code "105") (name "unconnected-(K26_3-Pad7)") (class "Default")
      (node (ref "K26_3") (pin "7") (pinfunction "7_7") (pintype "passive"))
    )
    (net (code "106") (name "unconnected-(K27_3-Pad2)") (class "Default")
      (node (ref "K27_3") (pin "2") (pinfunction "2_2") (pintype "passive"))
    )
    (net (code "107") (name "unconnected-(K27_3-Pad7)") (class "Default")
      (node (ref "K27_3") (pin "7") (pinfunction "7_7") (pintype "passive"))
    )
    (net (code "108") (name "unconnected-(K28_3-Pad2)") (class "Default")
      (node (ref "K28_3") (pin "2") (pinfunction "2_2") (pintype "passive"))
    )
    (net (code "109") (name "unconnected-(K28_3-Pad7)") (class "Default")
      (node (ref "K28_3") (pin "7") (pinfunction "7_7") (pintype "passive"))
    )
    (net (code "110") (name "unconnected-(K29_3-Pad2)") (class "Default")
      (node (ref "K29_3") (pin "2") (pinfunction "2_2") (pintype "passive"))
    )
    (net (code "111") (name "unconnected-(K29_3-Pad7)") (class "Default")
      (node (ref "K29_3") (pin "7") (pinfunction "7_7") (pintype "passive"))
    )
    (net (code "112") (name "unconnected-(K30_3-Pad2)") (class "Default")
      (node (ref "K30_3") (pin "2") (pinfunction "2_2") (pintype "passive"))
    )
    (net (code "113") (name "unconnected-(K30_3-Pad7)") (class "Default")
      (node (ref "K30_3") (pin "7") (pinfunction "7_7") (pintype "passive"))
    )
    (net (code "114") (name "unconnected-(K31_3-Pad2)") (class "Default")
      (node (ref "K31_3") (pin "2") (pinfunction "2_2") (pintype "passive"))
    )
    (net (code "115") (name "unconnected-(K31_3-Pad7)") (class "Default")
      (node (ref "K31_3") (pin "7") (pinfunction "7_7") (pintype "passive"))
    )
    (net (code "116") (name "unconnected-(K32_3-Pad2)") (class "Default")
      (node (ref "K32_3") (pin "2") (pinfunction "2_2") (pintype "passive"))
    )
    (net (code "117") (name "unconnected-(K32_3-Pad7)") (class "Default")
      (node (ref "K32_3") (pin "7") (pinfunction "7_7") (pintype "passive"))
    )
    (net (code "118") (name "unconnected-(K33_3-Pad2)") (class "Default")
      (node (ref "K33_3") (pin "2") (pinfunction "2_2") (pintype "passive"))
    )
    (net (code "119") (name "unconnected-(K33_3-Pad7)") (class "Default")
      (node (ref "K33_3") (pin "7") (pinfunction "7_7") (pintype "passive"))
    )
    (net (code "120") (name "unconnected-(K34_3-Pad2)") (class "Default")
      (node (ref "K34_3") (pin "2") (pinfunction "2_2") (pintype "passive"))
    )
    (net (code "121") (name "unconnected-(K34_3-Pad7)") (class "Default")
      (node (ref "K34_3") (pin "7") (pinfunction "7_7") (pintype "passive"))
    )
    (net (code "122") (name "unconnected-(K35_3-Pad2)") (class "Default")
      (node (ref "K35_3") (pin "2") (pinfunction "2_2") (pintype "passive"))
    )
    (net (code "123") (name "unconnected-(K35_3-Pad7)") (class "Default")
      (node (ref "K35_3") (pin "7") (pinfunction "7_7") (pintype "passive"))
    )
    (net (code "124") (name "unconnected-(K36_3-Pad2)") (class "Default")
      (node (ref "K36_3") (pin "2") (pinfunction "2_2") (pintype "passive"))
    )
    (net (code "125") (name "unconnected-(K36_3-Pad7)") (class "Default")
      (node (ref "K36_3") (pin "7") (pinfunction "7_7") (pintype "passive"))
    )
    (net (code "126") (name "unconnected-(K37_3-Pad2)") (class "Default")
      (node (ref "K37_3") (pin "2") (pinfunction "2_2") (pintype "passive"))
    )
    (net (code "127") (name "unconnected-(K37_3-Pad7)") (class "Default")
      (node (ref "K37_3") (pin "7") (pinfunction "7_7") (pintype "passive"))
    )
    (net (code "128") (name "unconnected-(K39_3-Pad2)") (class "Default")
      (node (ref "K39_3") (pin "2") (pinfunction "2_2") (pintype "passive"))
    )
    (net (code "129") (name "unconnected-(K39_3-Pad7)") (class "Default")
      (node (ref "K39_3") (pin "7") (pinfunction "7_7") (pintype "passive"))
    )
    (net (code "130") (name "unconnected-(K40_3-Pad2)") (class "Default")
      (node (ref "K40_3") (pin "2") (pinfunction "2_2") (pintype "passive"))
    )
    (net (code "131") (name "unconnected-(K40_3-Pad7)") (class "Default")
      (node (ref "K40_3") (pin "7") (pinfunction "7_7") (pintype "passive"))
    )
    (net (code "132") (name "unconnected-(K41_3-Pad2)") (class "Default")
      (node (ref "K41_3") (pin "2") (pinfunction "2_2") (pintype "passive"))
    )
    (net (code "133") (name "unconnected-(K41_3-Pad7)") (class "Default")
      (node (ref "K41_3") (pin "7") (pinfunction "7_7") (pintype "passive"))
    )
    (net (code "134") (name "unconnected-(K42_3-Pad2)") (class "Default")
      (node (ref "K42_3") (pin "2") (pinfunction "2_2") (pintype "passive"))
    )
    (net (code "135") (name "unconnected-(K42_3-Pad7)") (class "Default")
      (node (ref "K42_3") (pin "7") (pinfunction "7_7") (pintype "passive"))
    )
    (net (code "136") (name "unconnected-(K43_3-Pad2)") (class "Default")
      (node (ref "K43_3") (pin "2") (pinfunction "2_2") (pintype "passive"))
    )
    (net (code "137") (name "unconnected-(K43_3-Pad7)") (class "Default")
      (node (ref "K43_3") (pin "7") (pinfunction "7_7") (pintype "passive"))
    )
    (net (code "138") (name "unconnected-(K44_3-Pad2)") (class "Default")
      (node (ref "K44_3") (pin "2") (pinfunction "2_2") (pintype "passive"))
    )
    (net (code "139") (name "unconnected-(K44_3-Pad7)") (class "Default")
      (node (ref "K44_3") (pin "7") (pinfunction "7_7") (pintype "passive"))
    )
    (net (code "140") (name "unconnected-(K45_3-Pad2)") (class "Default")
      (node (ref "K45_3") (pin "2") (pinfunction "2_2") (pintype "passive"))
    )
    (net (code "141") (name "unconnected-(K45_3-Pad7)") (class "Default")
      (node (ref "K45_3") (pin "7") (pinfunction "7_7") (pintype "passive"))
    )
    (net (code "142") (name "unconnected-(K46_3-Pad2)") (class "Default")
      (node (ref "K46_3") (pin "2") (pinfunction "2_2") (pintype "passive"))
    )
    (net (code "143") (name "unconnected-(K46_3-Pad7)") (class "Default")
      (node (ref "K46_3") (pin "7") (pinfunction "7_7") (pintype "passive"))
    )
    (net (code "144") (name "unconnected-(K47_3-Pad2)") (class "Default")
      (node (ref "K47_3") (pin "2") (pinfunction "2_2") (pintype "passive"))
    )
    (net (code "145") (name "unconnected-(K47_3-Pad7)") (class "Default")
      (node (ref "K47_3") (pin "7") (pinfunction "7_7") (pintype "passive"))
    )
    (net (code "146") (name "unconnected-(K49_3-Pad2)") (class "Default")
      (node (ref "K49_3") (pin "2") (pinfunction "2_2") (pintype "passive"))
    )
    (net (code "147") (name "unconnected-(K49_3-Pad7)") (class "Default")
      (node (ref "K49_3") (pin "7") (pinfunction "7_7") (pintype "passive"))
    )
    (net (code "148") (name "unconnected-(K50_3-Pad2)") (class "Default")
      (node (ref "K50_3") (pin "2") (pinfunction "2_2") (pintype "passive"))
    )
    (net (code "149") (name "unconnected-(K50_3-Pad7)") (class "Default")
      (node (ref "K50_3") (pin "7") (pinfunction "7_7") (pintype "passive"))
    )
    (net (code "150") (name "unconnected-(K51_3-Pad2)") (class "Default")
      (node (ref "K51_3") (pin "2") (pinfunction "2_2") (pintype "passive"))
    )
    (net (code "151") (name "unconnected-(K51_3-Pad7)") (class "Default")
      (node (ref "K51_3") (pin "7") (pinfunction "7_7") (pintype "passive"))
    )
    (net (code "152") (name "unconnected-(K52_3-Pad2)") (class "Default")
      (node (ref "K52_3") (pin "2") (pinfunction "2_2") (pintype "passive"))
    )
    (net (code "153") (name "unconnected-(K52_3-Pad7)") (class "Default")
      (node (ref "K52_3") (pin "7") (pinfunction "7_7") (pintype "passive"))
    )
    (net (code "154") (name "unconnected-(K53_3-Pad2)") (class "Default")
      (node (ref "K53_3") (pin "2") (pinfunction "2_2") (pintype "passive"))
    )
    (net (code "155") (name "unconnected-(K53_3-Pad7)") (class "Default")
      (node (ref "K53_3") (pin "7") (pinfunction "7_7") (pintype "passive"))
    )
    (net (code "156") (name "unconnected-(K54_3-Pad2)") (class "Default")
      (node (ref "K54_3") (pin "2") (pinfunction "2_2") (pintype "passive"))
    )
    (net (code "157") (name "unconnected-(K54_3-Pad7)") (class "Default")
      (node (ref "K54_3") (pin "7") (pinfunction "7_7") (pintype "passive"))
    )
    (net (code "158") (name "unconnected-(K55_3-Pad2)") (class "Default")
      (node (ref "K55_3") (pin "2") (pinfunction "2_2") (pintype "passive"))
    )
    (net (code "159") (name "unconnected-(K55_3-Pad7)") (class "Default")
      (node (ref "K55_3") (pin "7") (pinfunction "7_7") (pintype "passive"))
    )
    (net (code "160") (name "unconnected-(K56_3-Pad2)") (class "Default")
      (node (ref "K56_3") (pin "2") (pinfunction "2_2") (pintype "passive"))
    )
    (net (code "161") (name "unconnected-(K56_3-Pad7)") (class "Default")
      (node (ref "K56_3") (pin "7") (pinfunction "7_7") (pintype "passive"))
    )
    (net (code "162") (name "unconnected-(K57_3-Pad2)") (class "Default")
      (node (ref "K57_3") (pin "2") (pinfunction "2_2") (pintype "passive"))
    )
    (net (code "163") (name "unconnected-(K57_3-Pad7)") (class "Default")
      (node (ref "K57_3") (pin "7") (pinfunction "7_7") (pintype "passive"))
    )
    (net (code "164") (name "unconnected-(K58_3-Pad2)") (class "Default")
      (node (ref "K58_3") (pin "2") (pinfunction "2_2") (pintype "passive"))
    )
    (net (code "165") (name "unconnected-(K58_3-Pad7)") (class "Default")
      (node (ref "K58_3") (pin "7") (pinfunction "7_7") (pintype "passive"))
    )
    (net (code "166") (name "unconnected-(K59_3-Pad2)") (class "Default")
      (node (ref "K59_3") (pin "2") (pinfunction "2_2") (pintype "passive"))
    )
    (net (code "167") (name "unconnected-(K59_3-Pad7)") (class "Default")
      (node (ref "K59_3") (pin "7") (pinfunction "7_7") (pintype "passive"))
    )
    (net (code "168") (name "unconnected-(K60_3-Pad2)") (class "Default")
      (node (ref "K60_3") (pin "2") (pinfunction "2_2") (pintype "passive"))
    )
    (net (code "169") (name "unconnected-(K60_3-Pad7)") (class "Default")
      (node (ref "K60_3") (pin "7") (pinfunction "7_7") (pintype "passive"))
    )
  )
)
